# Serial-7-Segment-Display.net
KiCad netlist of a schematic drawn in EAGLE
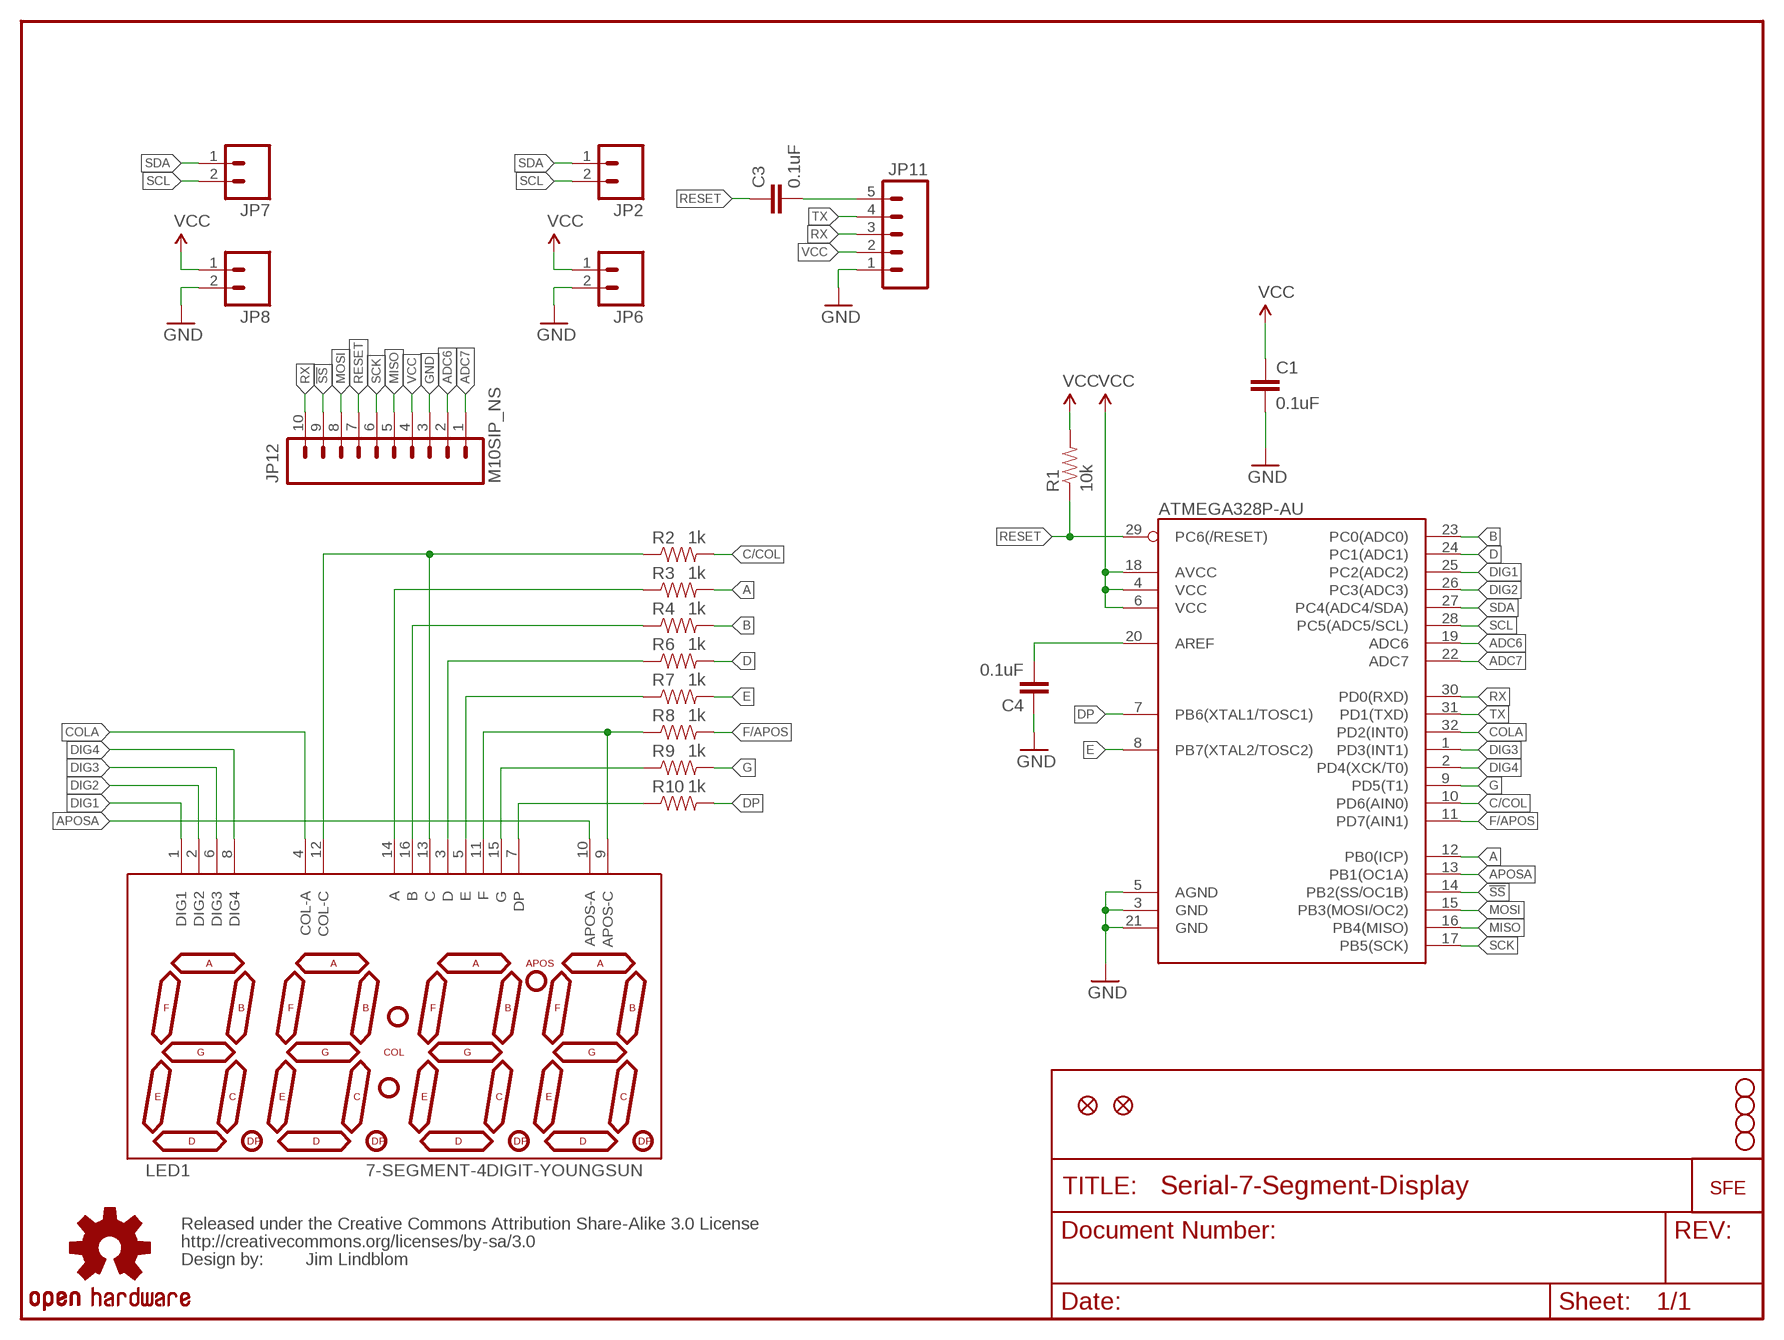
[diagram p0: schematic, sheet 1]

(export (version "E")
  (design (tool "Eeschema 10.0.6"))
  (components
    (comp (ref "ATMEGA328P-AU")
      (value "ATMEGA328P-AU")
      (footprint "eagle-import:TQFP32-08")
      (libsource (lib "eagle-import") (part "ATMEGA168"))
    )
    (comp (ref "C1")
      (value "0.1uF")
      (footprint "eagle-import:0402-CAP")
      (libsource (lib "eagle-import") (part "CAP0402-CAP"))
    )
    (comp (ref "C3")
      (value "0.1uF")
      (footprint "eagle-import:0402-CAP")
      (libsource (lib "eagle-import") (part "SparkFun-Passives_CAP0402-CAP"))
    )
    (comp (ref "C4")
      (value "0.1uF")
      (footprint "eagle-import:0402-CAP")
      (libsource (lib "eagle-import") (part "SparkFun-Passives_CAP0402-CAP"))
    )
    (comp (ref "JP1")
      (value "STAND-OFF")
      (footprint "eagle-import:STAND-OFF")
      (libsource (lib "eagle-import") (part "STAND-OFF"))
    )
    (comp (ref "JP2")
      (value "M021X02_NO_SILK")
      (footprint "eagle-import:1X02_NO_SILK")
      (libsource (lib "eagle-import") (part "M021X02_NO_SILK"))
    )
    (comp (ref "JP3")
      (value "STAND-OFF")
      (footprint "eagle-import:STAND-OFF")
      (libsource (lib "eagle-import") (part "STAND-OFF"))
    )
    (comp (ref "JP4")
      (value "STAND-OFF")
      (footprint "eagle-import:STAND-OFF")
      (libsource (lib "eagle-import") (part "STAND-OFF"))
    )
    (comp (ref "JP5")
      (value "STAND-OFF")
      (footprint "eagle-import:STAND-OFF")
      (libsource (lib "eagle-import") (part "STAND-OFF"))
    )
    (comp (ref "JP6")
      (value "M021X02_NO_SILK")
      (footprint "eagle-import:1X02_NO_SILK")
      (libsource (lib "eagle-import") (part "M021X02_NO_SILK"))
    )
    (comp (ref "JP7")
      (value "M021X02_NO_SILK")
      (footprint "eagle-import:1X02_NO_SILK")
      (libsource (lib "eagle-import") (part "M021X02_NO_SILK"))
    )
    (comp (ref "JP8")
      (value "M021X02_NO_SILK")
      (footprint "eagle-import:1X02_NO_SILK")
      (libsource (lib "eagle-import") (part "M021X02_NO_SILK"))
    )
    (comp (ref "JP9")
      (value "FIDUCIALUFIDUCIAL")
      (footprint "eagle-import:MICRO-FIDUCIAL")
      (libsource (lib "eagle-import") (part "FIDUCIALUFIDUCIAL"))
    )
    (comp (ref "JP10")
      (value "FIDUCIALUFIDUCIAL")
      (footprint "eagle-import:MICRO-FIDUCIAL")
      (libsource (lib "eagle-import") (part "FIDUCIALUFIDUCIAL"))
    )
    (comp (ref "JP11")
      (value "M05PTH-NS")
      (footprint "eagle-import:1X05_NO_SILK")
      (libsource (lib "eagle-import") (part "M05PTH-NS"))
    )
    (comp (ref "JP12")
      (value "M10SIP_NS")
      (footprint "eagle-import:1X10_NO_SILK")
      (libsource (lib "eagle-import") (part "M10SIP_NS"))
    )
    (comp (ref "LED1")
      (value "7-SEGMENT-4DIGIT-YOUNGSUN")
      (footprint "eagle-import:7-SEGMENT-4DIGIT-YOUNGSUN")
      (libsource (lib "eagle-import") (part "7-SEGMENT-4DIGIT-YOUNGSUN"))
    )
    (comp (ref "R1")
      (value "10k")
      (footprint "eagle-import:0402-RES")
      (libsource (lib "eagle-import") (part "RESISTOR0402-RES"))
    )
    (comp (ref "R2")
      (value "1k")
      (footprint "eagle-import:0402-RES")
      (libsource (lib "eagle-import") (part "RESISTOR0402-RES"))
    )
    (comp (ref "R3")
      (value "1k")
      (footprint "eagle-import:0402-RES")
      (libsource (lib "eagle-import") (part "RESISTOR0402-RES"))
    )
    (comp (ref "R4")
      (value "1k")
      (footprint "eagle-import:0402-RES")
      (libsource (lib "eagle-import") (part "RESISTOR0402-RES"))
    )
    (comp (ref "R6")
      (value "1k")
      (footprint "eagle-import:0402-RES")
      (libsource (lib "eagle-import") (part "RESISTOR0402-RES"))
    )
    (comp (ref "R7")
      (value "1k")
      (footprint "eagle-import:0402-RES")
      (libsource (lib "eagle-import") (part "RESISTOR0402-RES"))
    )
    (comp (ref "R8")
      (value "1k")
      (footprint "eagle-import:0402-RES")
      (libsource (lib "eagle-import") (part "RESISTOR0402-RES"))
    )
    (comp (ref "R9")
      (value "1k")
      (footprint "eagle-import:0402-RES")
      (libsource (lib "eagle-import") (part "RESISTOR0402-RES"))
    )
    (comp (ref "R10")
      (value "1k")
      (footprint "eagle-import:0402-RES")
      (libsource (lib "eagle-import") (part "RESISTOR0402-RES"))
    )
    (comp (ref "U$1")
      (value "CREATIVE_COMMONS")
      (footprint "eagle-import:CREATIVE_COMMONS")
      (libsource (lib "eagle-import") (part "CREATIVE_COMMONS"))
    )
    (comp (ref "U$2")
      (value "LOGO-SFESK")
      (footprint "eagle-import:SFE-LOGO-FLAME")
      (libsource (lib "eagle-import") (part "LOGO-SFESK"))
    )
    (comp (ref "U$4")
      (value "OSHW-LOGOS")
      (footprint "eagle-import:OSHW-LOGO-S")
      (libsource (lib "eagle-import") (part "OSHW-LOGOS"))
    )
  )
  (nets
    (net (code "1") (name "/~{SS}") (class "Default")
      (node (ref "ATMEGA328P-AU") (pin "14") (pinfunction "PB2(SS/OC1B)_14") (pintype "bidirectional"))
      (node (ref "JP12") (pin "9") (pinfunction "9_9") (pintype "passive"))
    )
    (net (code "2") (name "A") (class "Default")
      (node (ref "ATMEGA328P-AU") (pin "12") (pinfunction "PB0(ICP)_12") (pintype "bidirectional"))
      (node (ref "R3") (pin "2") (pinfunction "2_2") (pintype "passive"))
    )
    (net (code "3") (name "ADC6") (class "Default")
      (node (ref "ATMEGA328P-AU") (pin "19") (pinfunction "ADC6_19") (pintype "bidirectional"))
      (node (ref "JP12") (pin "2") (pinfunction "2_2") (pintype "passive"))
    )
    (net (code "4") (name "ADC7") (class "Default")
      (node (ref "ATMEGA328P-AU") (pin "22") (pinfunction "ADC7_22") (pintype "bidirectional"))
      (node (ref "JP12") (pin "1") (pinfunction "1_1") (pintype "passive"))
    )
    (net (code "5") (name "APOSA") (class "Default")
      (node (ref "ATMEGA328P-AU") (pin "13") (pinfunction "PB1(OC1A)_13") (pintype "bidirectional"))
      (node (ref "LED1") (pin "10") (pinfunction "APOS-A_10") (pintype "bidirectional"))
    )
    (net (code "6") (name "B") (class "Default")
      (node (ref "ATMEGA328P-AU") (pin "23") (pinfunction "PC0(ADC0)_23") (pintype "bidirectional"))
      (node (ref "R4") (pin "2") (pinfunction "2_2") (pintype "passive"))
    )
    (net (code "7") (name "COLA") (class "Default")
      (node (ref "ATMEGA328P-AU") (pin "32") (pinfunction "PD2(INT0)_32") (pintype "bidirectional"))
      (node (ref "LED1") (pin "4") (pinfunction "COL-A_4") (pintype "bidirectional"))
    )
    (net (code "8") (name "C{slash}COL") (class "Default")
      (node (ref "ATMEGA328P-AU") (pin "10") (pinfunction "PD6(AIN0)_10") (pintype "bidirectional"))
      (node (ref "R2") (pin "2") (pinfunction "2_2") (pintype "passive"))
    )
    (net (code "9") (name "D") (class "Default")
      (node (ref "ATMEGA328P-AU") (pin "24") (pinfunction "PC1(ADC1)_24") (pintype "bidirectional"))
      (node (ref "R6") (pin "2") (pinfunction "2_2") (pintype "passive"))
    )
    (net (code "10") (name "DIG1") (class "Default")
      (node (ref "ATMEGA328P-AU") (pin "25") (pinfunction "PC2(ADC2)_25") (pintype "bidirectional"))
      (node (ref "LED1") (pin "1") (pinfunction "DIG1_1") (pintype "bidirectional"))
    )
    (net (code "11") (name "DIG2") (class "Default")
      (node (ref "ATMEGA328P-AU") (pin "26") (pinfunction "PC3(ADC3)_26") (pintype "bidirectional"))
      (node (ref "LED1") (pin "2") (pinfunction "DIG2_2") (pintype "bidirectional"))
    )
    (net (code "12") (name "DIG3") (class "Default")
      (node (ref "ATMEGA328P-AU") (pin "1") (pinfunction "PD3(INT1)_1") (pintype "bidirectional"))
      (node (ref "LED1") (pin "6") (pinfunction "DIG3_6") (pintype "bidirectional"))
    )
    (net (code "13") (name "DIG4") (class "Default")
      (node (ref "ATMEGA328P-AU") (pin "2") (pinfunction "PD4(XCK/T0)_2") (pintype "bidirectional"))
      (node (ref "LED1") (pin "8") (pinfunction "DIG4_8") (pintype "bidirectional"))
    )
    (net (code "14") (name "DP") (class "Default")
      (node (ref "ATMEGA328P-AU") (pin "7") (pinfunction "PB6(XTAL1/TOSC1)_7") (pintype "bidirectional"))
      (node (ref "R10") (pin "2") (pinfunction "2_2") (pintype "passive"))
    )
    (net (code "15") (name "E") (class "Default")
      (node (ref "ATMEGA328P-AU") (pin "8") (pinfunction "PB7(XTAL2/TOSC2)_8") (pintype "bidirectional"))
      (node (ref "R7") (pin "2") (pinfunction "2_2") (pintype "passive"))
    )
    (net (code "16") (name "F{slash}APOS") (class "Default")
      (node (ref "ATMEGA328P-AU") (pin "11") (pinfunction "PD7(AIN1)_11") (pintype "bidirectional"))
      (node (ref "R8") (pin "2") (pinfunction "2_2") (pintype "passive"))
    )
    (net (code "17") (name "G") (class "Default")
      (node (ref "ATMEGA328P-AU") (pin "9") (pinfunction "PD5(T1)_9") (pintype "bidirectional"))
      (node (ref "R9") (pin "2") (pinfunction "2_2") (pintype "passive"))
    )
    (net (code "18") (name "GND") (class "Default")
      (node (ref "ATMEGA328P-AU") (pin "21") (pinfunction "GND_21") (pintype "bidirectional"))
      (node (ref "ATMEGA328P-AU") (pin "3") (pinfunction "GND_3") (pintype "bidirectional"))
      (node (ref "ATMEGA328P-AU") (pin "5") (pinfunction "AGND_5") (pintype "bidirectional"))
      (node (ref "C1") (pin "2") (pinfunction "2_2") (pintype "passive"))
      (node (ref "C4") (pin "1") (pinfunction "1_1") (pintype "passive"))
      (node (ref "JP11") (pin "1") (pinfunction "1_1") (pintype "passive"))
      (node (ref "JP12") (pin "3") (pinfunction "3_3") (pintype "passive"))
      (node (ref "JP6") (pin "2") (pinfunction "2_2") (pintype "passive"))
      (node (ref "JP8") (pin "2") (pinfunction "2_2") (pintype "passive"))
    )
    (net (code "19") (name "MISO") (class "Default")
      (node (ref "ATMEGA328P-AU") (pin "16") (pinfunction "PB4(MISO)_16") (pintype "bidirectional"))
      (node (ref "JP12") (pin "5") (pinfunction "5_5") (pintype "passive"))
    )
    (net (code "20") (name "MOSI") (class "Default")
      (node (ref "ATMEGA328P-AU") (pin "15") (pinfunction "PB3(MOSI/OC2)_15") (pintype "bidirectional"))
      (node (ref "JP12") (pin "8") (pinfunction "8_8") (pintype "passive"))
    )
    (net (code "21") (name "Net-(ATMEGA328P-AU-AREF)") (class "Default")
      (node (ref "ATMEGA328P-AU") (pin "20") (pinfunction "AREF_20") (pintype "bidirectional"))
      (node (ref "C4") (pin "2") (pinfunction "2_2") (pintype "passive"))
    )
    (net (code "22") (name "Net-(C3-Pad2)") (class "Default")
      (node (ref "C3") (pin "2") (pinfunction "2_2") (pintype "passive"))
      (node (ref "JP11") (pin "5") (pinfunction "5_5") (pintype "passive"))
    )
    (net (code "23") (name "Net-(LED1-A)") (class "Default")
      (node (ref "LED1") (pin "14") (pinfunction "A_14") (pintype "bidirectional"))
      (node (ref "R3") (pin "1") (pinfunction "1_1") (pintype "passive"))
    )
    (net (code "24") (name "Net-(LED1-APOS-C)") (class "Default")
      (node (ref "LED1") (pin "11") (pinfunction "F_11") (pintype "bidirectional"))
      (node (ref "LED1") (pin "9") (pinfunction "APOS-C_9") (pintype "bidirectional"))
      (node (ref "R8") (pin "1") (pinfunction "1_1") (pintype "passive"))
    )
    (net (code "25") (name "Net-(LED1-B)") (class "Default")
      (node (ref "LED1") (pin "16") (pinfunction "B_16") (pintype "bidirectional"))
      (node (ref "R4") (pin "1") (pinfunction "1_1") (pintype "passive"))
    )
    (net (code "26") (name "Net-(LED1-C)") (class "Default")
      (node (ref "LED1") (pin "12") (pinfunction "COL-C_12") (pintype "bidirectional"))
      (node (ref "LED1") (pin "13") (pinfunction "C_13") (pintype "bidirectional"))
      (node (ref "R2") (pin "1") (pinfunction "1_1") (pintype "passive"))
    )
    (net (code "27") (name "Net-(LED1-D)") (class "Default")
      (node (ref "LED1") (pin "3") (pinfunction "D_3") (pintype "bidirectional"))
      (node (ref "R6") (pin "1") (pinfunction "1_1") (pintype "passive"))
    )
    (net (code "28") (name "Net-(LED1-DP)") (class "Default")
      (node (ref "LED1") (pin "7") (pinfunction "DP_7") (pintype "bidirectional"))
      (node (ref "R10") (pin "1") (pinfunction "1_1") (pintype "passive"))
    )
    (net (code "29") (name "Net-(LED1-E)") (class "Default")
      (node (ref "LED1") (pin "5") (pinfunction "E_5") (pintype "bidirectional"))
      (node (ref "R7") (pin "1") (pinfunction "1_1") (pintype "passive"))
    )
    (net (code "30") (name "Net-(LED1-G)") (class "Default")
      (node (ref "LED1") (pin "15") (pinfunction "G_15") (pintype "bidirectional"))
      (node (ref "R9") (pin "1") (pinfunction "1_1") (pintype "passive"))
    )
    (net (code "31") (name "RESET") (class "Default")
      (node (ref "ATMEGA328P-AU") (pin "29") (pinfunction "PC6(/RESET)_29") (pintype "bidirectional"))
      (node (ref "C3") (pin "1") (pinfunction "1_1") (pintype "passive"))
      (node (ref "JP12") (pin "7") (pinfunction "7_7") (pintype "passive"))
      (node (ref "R1") (pin "1") (pinfunction "1_1") (pintype "passive"))
    )
    (net (code "32") (name "RX") (class "Default")
      (node (ref "ATMEGA328P-AU") (pin "30") (pinfunction "PD0(RXD)_30") (pintype "bidirectional"))
      (node (ref "JP11") (pin "3") (pinfunction "3_3") (pintype "passive"))
      (node (ref "JP12") (pin "10") (pinfunction "10_10") (pintype "passive"))
    )
    (net (code "33") (name "SCK") (class "Default")
      (node (ref "ATMEGA328P-AU") (pin "17") (pinfunction "PB5(SCK)_17") (pintype "bidirectional"))
      (node (ref "JP12") (pin "6") (pinfunction "6_6") (pintype "passive"))
    )
    (net (code "34") (name "SCL") (class "Default")
      (node (ref "ATMEGA328P-AU") (pin "28") (pinfunction "PC5(ADC5/SCL)_28") (pintype "bidirectional"))
      (node (ref "JP2") (pin "2") (pinfunction "2_2") (pintype "passive"))
      (node (ref "JP7") (pin "2") (pinfunction "2_2") (pintype "passive"))
    )
    (net (code "35") (name "SDA") (class "Default")
      (node (ref "ATMEGA328P-AU") (pin "27") (pinfunction "PC4(ADC4/SDA)_27") (pintype "bidirectional"))
      (node (ref "JP2") (pin "1") (pinfunction "1_1") (pintype "passive"))
      (node (ref "JP7") (pin "1") (pinfunction "1_1") (pintype "passive"))
    )
    (net (code "36") (name "TX") (class "Default")
      (node (ref "ATMEGA328P-AU") (pin "31") (pinfunction "PD1(TXD)_31") (pintype "bidirectional"))
      (node (ref "JP11") (pin "4") (pinfunction "4_4") (pintype "passive"))
    )
    (net (code "37") (name "VCC") (class "Default")
      (node (ref "ATMEGA328P-AU") (pin "18") (pinfunction "AVCC_18") (pintype "bidirectional"))
      (node (ref "ATMEGA328P-AU") (pin "4") (pinfunction "VCC_4") (pintype "bidirectional"))
      (node (ref "ATMEGA328P-AU") (pin "6") (pinfunction "VCC_6") (pintype "bidirectional"))
      (node (ref "C1") (pin "1") (pinfunction "1_1") (pintype "passive"))
      (node (ref "JP11") (pin "2") (pinfunction "2_2") (pintype "passive"))
      (node (ref "JP12") (pin "4") (pinfunction "4_4") (pintype "passive"))
      (node (ref "JP6") (pin "1") (pinfunction "1_1") (pintype "passive"))
      (node (ref "JP8") (pin "1") (pinfunction "1_1") (pintype "passive"))
      (node (ref "R1") (pin "2") (pinfunction "2_2") (pintype "passive"))
    )
  )
)
